# Qwiic_GPS-RTK2_-_ublox_ZED-F9P.net
KiCad netlist of a schematic drawn in EAGLE
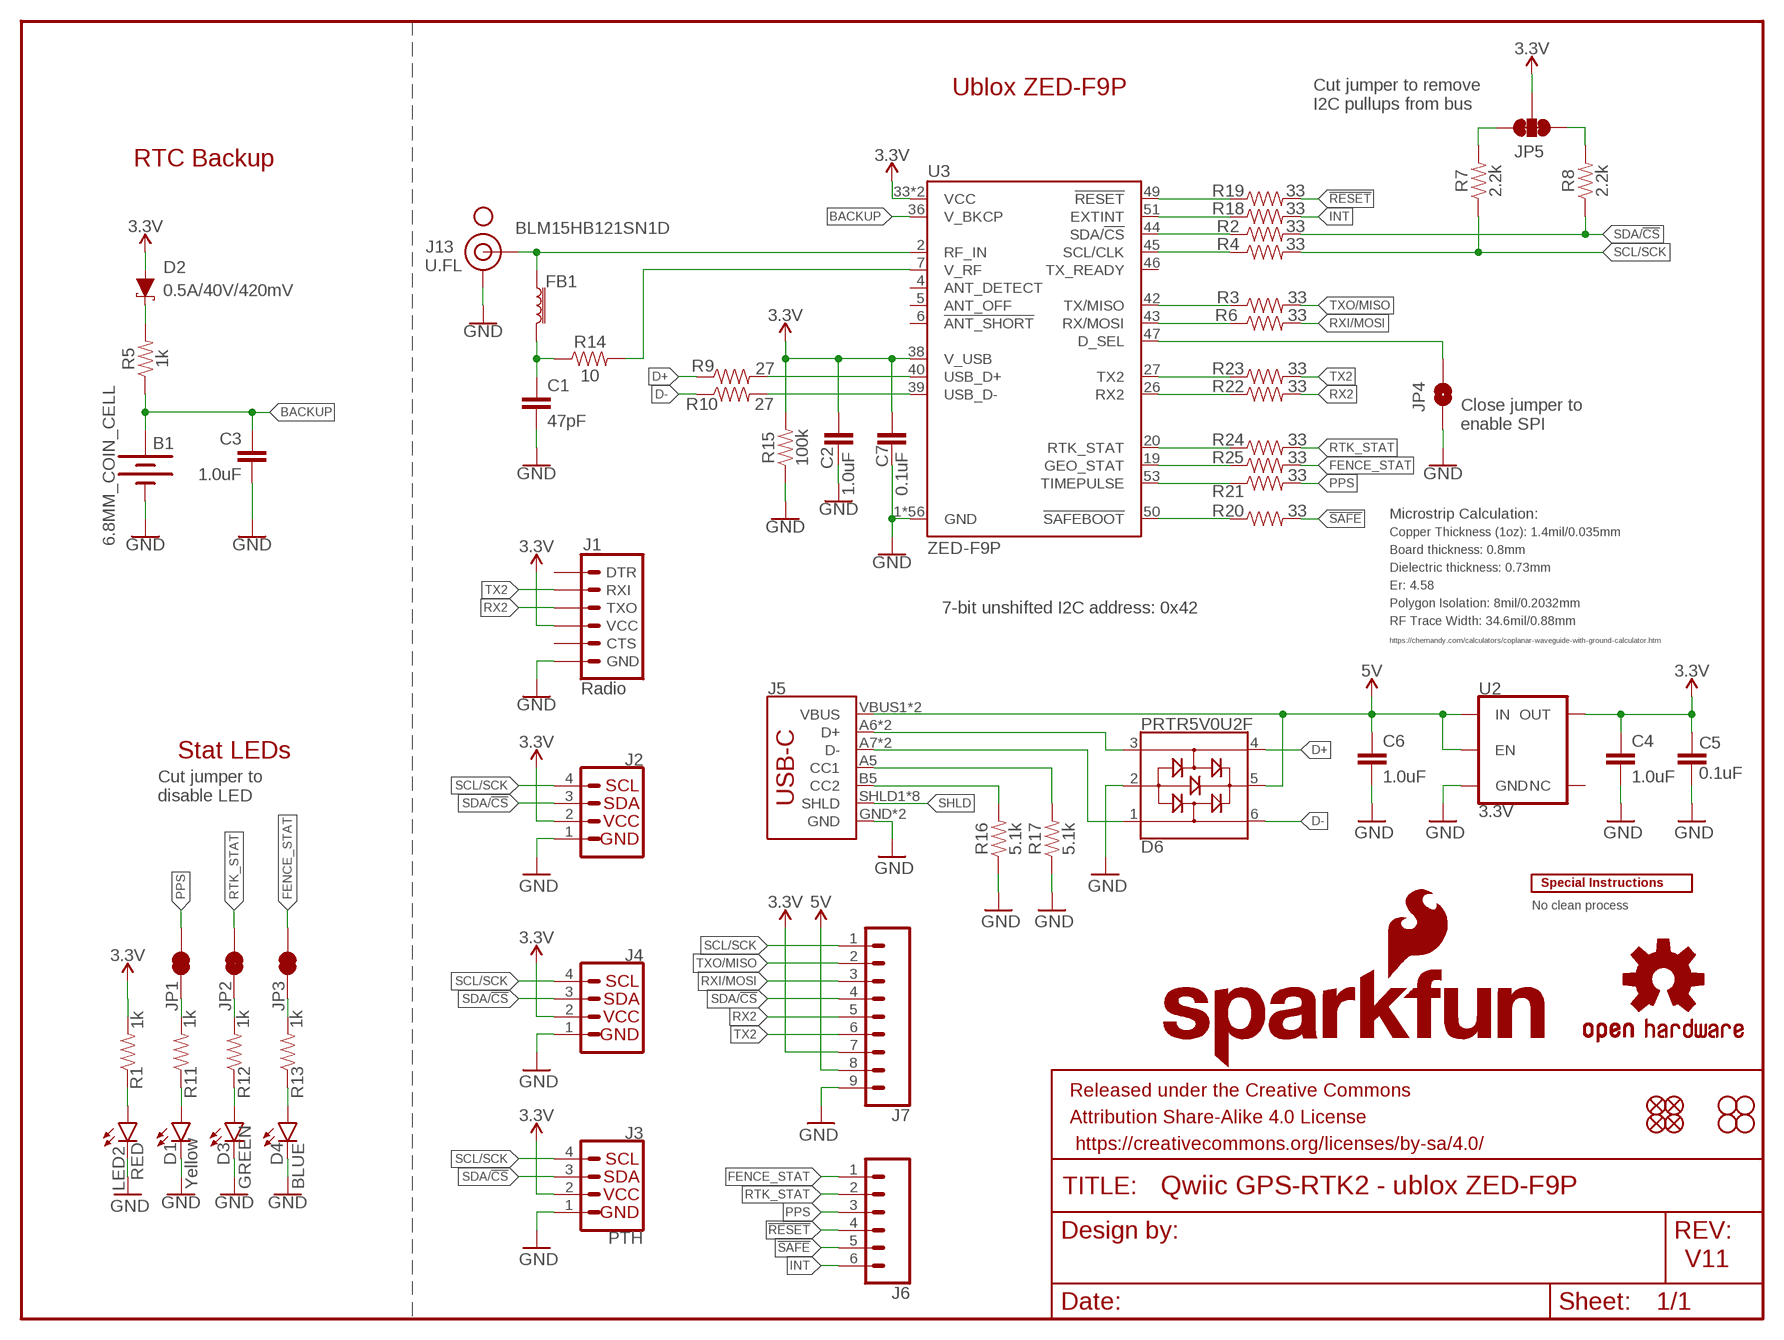
[diagram p0: schematic, sheet 1]

(export (version "E")
  (design (tool "Eeschema 10.0.6"))
  (components
    (comp (ref "B1")
      (value "6.8MM_COIN_CELL")
      (footprint "eagle-import:BATTCON-6.8MM")
      (libsource (lib "eagle-import") (part "BATTERY-6.8MM_SMD"))
    )
    (comp (ref "C1")
      (value "47pF")
      (footprint "eagle-import:0603")
      (libsource (lib "eagle-import") (part "47PF-0603-50V-5%"))
    )
    (comp (ref "C2")
      (value "1.0uF")
      (footprint "eagle-import:0603")
      (libsource (lib "eagle-import") (part "1.0UF-0603-16V-10%"))
    )
    (comp (ref "C3")
      (value "1.0uF")
      (footprint "eagle-import:0603")
      (libsource (lib "eagle-import") (part "1.0UF-0603-16V-10%"))
    )
    (comp (ref "C4")
      (value "1.0uF")
      (footprint "eagle-import:0603")
      (libsource (lib "eagle-import") (part "1.0UF-0603-16V-10%"))
    )
    (comp (ref "C5")
      (value "0.1uF")
      (footprint "eagle-import:0603")
      (libsource (lib "eagle-import") (part "0.1UF-0603-25V-(+80/-20%)"))
    )
    (comp (ref "C6")
      (value "1.0uF")
      (footprint "eagle-import:0603")
      (libsource (lib "eagle-import") (part "1.0UF-0603-16V-10%"))
    )
    (comp (ref "C7")
      (value "0.1uF")
      (footprint "eagle-import:0603")
      (libsource (lib "eagle-import") (part "0.1UF-0603-25V-(+80/-20%)"))
    )
    (comp (ref "D1")
      (value "Yellow")
      (footprint "eagle-import:LED-0603")
      (libsource (lib "eagle-import") (part "LED-YELLOW0603"))
    )
    (comp (ref "D2")
      (value "0.5A/40V/420mV")
      (footprint "eagle-import:SOD-323")
      (libsource (lib "eagle-import") (part "DIODE-SCHOTTKY-PMEG4005EJ"))
    )
    (comp (ref "D3")
      (value "GREEN")
      (footprint "eagle-import:LED-0603")
      (libsource (lib "eagle-import") (part "LED-GREEN0603"))
    )
    (comp (ref "D4")
      (value "BLUE")
      (footprint "eagle-import:LED-0603")
      (libsource (lib "eagle-import") (part "LED-BLUE0603"))
    )
    (comp (ref "D6")
      (value "PRTR5V0U2F")
      (footprint "eagle-import:SOT886")
      (libsource (lib "eagle-import") (part "PRTR5V0U2F"))
    )
    (comp (ref "FB1")
      (value "FERRITE_BEAD-120_OHM-0402")
      (footprint "eagle-import:0402")
      (fields (field (name "MFG_PART") "BLM15HB121SN1D"))
      (libsource (lib "eagle-import") (part "FERRITE_BEAD-120_OHM-0402"))
    )
    (comp (ref "FRAME1")
      (value "FRAME-LETTER")
      (footprint "eagle-import:CREATIVE_COMMONS")
      (libsource (lib "eagle-import") (part "FRAME-LETTER"))
    )
    (comp (ref "J1")
      (value "Radio")
      (footprint "eagle-import:1X06_NO_SILK")
      (libsource (lib "eagle-import") (part "6_PIN_SERIAL_TARGET_NO_SILK"))
    )
    (comp (ref "J2")
      (value "I2C_STANDARDQWIIC")
      (footprint "eagle-import:1X04_1MM_RA")
      (libsource (lib "eagle-import") (part "I2C_STANDARDQWIIC"))
    )
    (comp (ref "J3")
      (value "PTH")
      (footprint "eagle-import:1X04_NO_SILK")
      (libsource (lib "eagle-import") (part "SparkX_I2C_STANDARD_NO_SILK"))
    )
    (comp (ref "J4")
      (value "I2C_STANDARDQWIIC")
      (footprint "eagle-import:1X04_1MM_RA")
      (libsource (lib "eagle-import") (part "I2C_STANDARDQWIIC"))
    )
    (comp (ref "J5")
      (value "USB_C16PIN")
      (footprint "eagle-import:USB-C-16P")
      (libsource (lib "eagle-import") (part "USB_C16PIN"))
    )
    (comp (ref "J6")
      (value "CONN_06NO_SILK_FEMALE_PTH")
      (footprint "eagle-import:1X06_NO_SILK")
      (libsource (lib "eagle-import") (part "CONN_06NO_SILK_FEMALE_PTH"))
    )
    (comp (ref "J7")
      (value "CONN_09NO_SILK")
      (footprint "eagle-import:1X09_NO_SILK")
      (libsource (lib "eagle-import") (part "CONN_09NO_SILK"))
    )
    (comp (ref "J13")
      (value "U.FL")
      (footprint "eagle-import:U.FL")
      (libsource (lib "eagle-import") (part "U.FL2PIN"))
    )
    (comp (ref "JP1")
      (value "JUMPER-SMT_2_NC_TRACE_SILK")
      (footprint "eagle-import:SMT-JUMPER_2_NC_TRACE_SILK")
      (libsource (lib "eagle-import") (part "JUMPER-SMT_2_NC_TRACE_SILK"))
    )
    (comp (ref "JP2")
      (value "JUMPER-SMT_2_NC_TRACE_SILK")
      (footprint "eagle-import:SMT-JUMPER_2_NC_TRACE_SILK")
      (libsource (lib "eagle-import") (part "JUMPER-SMT_2_NC_TRACE_SILK"))
    )
    (comp (ref "JP3")
      (value "JUMPER-SMT_2_NC_TRACE_SILK")
      (footprint "eagle-import:SMT-JUMPER_2_NC_TRACE_SILK")
      (libsource (lib "eagle-import") (part "JUMPER-SMT_2_NC_TRACE_SILK"))
    )
    (comp (ref "JP4")
      (value "JUMPER-SMT_2_NO_SILK")
      (footprint "eagle-import:SMT-JUMPER_2_NO_SILK")
      (libsource (lib "eagle-import") (part "JUMPER-SMT_2_NO_SILK"))
    )
    (comp (ref "JP5")
      (value "JUMPER-SMT_3_2-NC_TRACE_SILK")
      (footprint "eagle-import:SMT-JUMPER_3_2-NC_TRACE_SILK")
      (libsource (lib "eagle-import") (part "JUMPER-SMT_3_2-NC_TRACE_SILK"))
    )
    (comp (ref "JP21")
      (value "FIDUCIALUFIDUCIAL")
      (footprint "eagle-import:MICRO-FIDUCIAL")
      (libsource (lib "eagle-import") (part "FIDUCIALUFIDUCIAL"))
    )
    (comp (ref "JP31")
      (value "STAND-OFF")
      (footprint "eagle-import:STAND-OFF")
      (libsource (lib "eagle-import") (part "STAND-OFF"))
    )
    (comp (ref "JP41")
      (value "STAND-OFF")
      (footprint "eagle-import:STAND-OFF")
      (libsource (lib "eagle-import") (part "STAND-OFF"))
    )
    (comp (ref "JP61")
      (value "FIDUCIALUFIDUCIAL")
      (footprint "eagle-import:MICRO-FIDUCIAL")
      (libsource (lib "eagle-import") (part "FIDUCIALUFIDUCIAL"))
    )
    (comp (ref "JP71")
      (value "FIDUCIALUFIDUCIAL")
      (footprint "eagle-import:MICRO-FIDUCIAL")
      (libsource (lib "eagle-import") (part "FIDUCIALUFIDUCIAL"))
    )
    (comp (ref "JP81")
      (value "FIDUCIALUFIDUCIAL")
      (footprint "eagle-import:MICRO-FIDUCIAL")
      (libsource (lib "eagle-import") (part "FIDUCIALUFIDUCIAL"))
    )
    (comp (ref "JP91")
      (value "STAND-OFF")
      (footprint "eagle-import:STAND-OFF")
      (libsource (lib "eagle-import") (part "STAND-OFF"))
    )
    (comp (ref "JP101")
      (value "STAND-OFF")
      (footprint "eagle-import:STAND-OFF")
      (libsource (lib "eagle-import") (part "STAND-OFF"))
    )
    (comp (ref "LED2")
      (value "RED")
      (footprint "eagle-import:LED-0603")
      (libsource (lib "eagle-import") (part "LED-RED0603"))
    )
    (comp (ref "LOGO1")
      (value "OSHW-LOGOMINI")
      (footprint "eagle-import:OSHW-LOGO-MINI")
      (libsource (lib "eagle-import") (part "OSHW-LOGOMINI"))
    )
    (comp (ref "LOGO2")
      (value "SFE_LOGO_NAME_FLAME.1_INCH")
      (footprint "eagle-import:SFE_LOGO_NAME_FLAME_.1")
      (libsource (lib "eagle-import") (part "SFE_LOGO_NAME_FLAME.1_INCH"))
    )
    (comp (ref "R1")
      (value "1k")
      (footprint "eagle-import:0603")
      (libsource (lib "eagle-import") (part "1KOHM-0603-1/10W-1%"))
    )
    (comp (ref "R2")
      (value "33")
      (footprint "eagle-import:0603")
      (libsource (lib "eagle-import") (part "33OHM-0603-1/10W-1%"))
    )
    (comp (ref "R3")
      (value "33")
      (footprint "eagle-import:0603")
      (libsource (lib "eagle-import") (part "33OHM-0603-1/10W-1%"))
    )
    (comp (ref "R4")
      (value "33")
      (footprint "eagle-import:0603")
      (libsource (lib "eagle-import") (part "33OHM-0603-1/10W-1%"))
    )
    (comp (ref "R5")
      (value "1k")
      (footprint "eagle-import:0603")
      (libsource (lib "eagle-import") (part "1KOHM-0603-1/10W-1%"))
    )
    (comp (ref "R6")
      (value "33")
      (footprint "eagle-import:0603")
      (libsource (lib "eagle-import") (part "33OHM-0603-1/10W-1%"))
    )
    (comp (ref "R7")
      (value "2.2k")
      (footprint "eagle-import:0603")
      (libsource (lib "eagle-import") (part "2.2KOHM-0603-1/10W-1%"))
    )
    (comp (ref "R8")
      (value "2.2k")
      (footprint "eagle-import:0603")
      (libsource (lib "eagle-import") (part "2.2KOHM-0603-1/10W-1%"))
    )
    (comp (ref "R9")
      (value "27")
      (footprint "eagle-import:0603")
      (libsource (lib "eagle-import") (part "27OHM-0603-1/10W-1%"))
    )
    (comp (ref "R10")
      (value "27")
      (footprint "eagle-import:0603")
      (libsource (lib "eagle-import") (part "27OHM-0603-1/10W-1%"))
    )
    (comp (ref "R11")
      (value "1k")
      (footprint "eagle-import:0603")
      (libsource (lib "eagle-import") (part "1KOHM-0603-1/10W-1%"))
    )
    (comp (ref "R12")
      (value "1k")
      (footprint "eagle-import:0603")
      (libsource (lib "eagle-import") (part "1KOHM-0603-1/10W-1%"))
    )
    (comp (ref "R13")
      (value "1k")
      (footprint "eagle-import:0603")
      (libsource (lib "eagle-import") (part "1KOHM-0603-1/10W-1%"))
    )
    (comp (ref "R14")
      (value "10")
      (footprint "eagle-import:0603")
      (libsource (lib "eagle-import") (part "10OHM-0603-1/10W-1%"))
    )
    (comp (ref "R15")
      (value "100k")
      (footprint "eagle-import:0603")
      (libsource (lib "eagle-import") (part "100KOHM-0603-1/10W-1%"))
    )
    (comp (ref "R16")
      (value "5.1k")
      (footprint "eagle-import:0603")
      (libsource (lib "eagle-import") (part "5.1KOHM5.1KOHM-0603-1/10W-1%"))
    )
    (comp (ref "R17")
      (value "5.1k")
      (footprint "eagle-import:0603")
      (libsource (lib "eagle-import") (part "5.1KOHM5.1KOHM-0603-1/10W-1%"))
    )
    (comp (ref "R18")
      (value "33")
      (footprint "eagle-import:0603")
      (libsource (lib "eagle-import") (part "33OHM-0603-1/10W-1%"))
    )
    (comp (ref "R19")
      (value "33")
      (footprint "eagle-import:0603")
      (libsource (lib "eagle-import") (part "33OHM-0603-1/10W-1%"))
    )
    (comp (ref "R20")
      (value "33")
      (footprint "eagle-import:0603")
      (libsource (lib "eagle-import") (part "33OHM-0603-1/10W-1%"))
    )
    (comp (ref "R21")
      (value "33")
      (footprint "eagle-import:0603")
      (libsource (lib "eagle-import") (part "33OHM-0603-1/10W-1%"))
    )
    (comp (ref "R22")
      (value "33")
      (footprint "eagle-import:0603")
      (libsource (lib "eagle-import") (part "33OHM-0603-1/10W-1%"))
    )
    (comp (ref "R23")
      (value "33")
      (footprint "eagle-import:0603")
      (libsource (lib "eagle-import") (part "33OHM-0603-1/10W-1%"))
    )
    (comp (ref "R24")
      (value "33")
      (footprint "eagle-import:0603")
      (libsource (lib "eagle-import") (part "33OHM-0603-1/10W-1%"))
    )
    (comp (ref "R25")
      (value "33")
      (footprint "eagle-import:0603")
      (libsource (lib "eagle-import") (part "33OHM-0603-1/10W-1%"))
    )
    (comp (ref "U$2")
      (value "SPECIAL_INSTRUCTIONS-ORDERING")
      (footprint "eagle-import:ORDERING_INSTRUCTIONS")
      (libsource (lib "eagle-import") (part "SPECIAL_INSTRUCTIONS-ORDERING"))
    )
    (comp (ref "U$54")
      (value "SMA-ANTENNA-THREADED")
      (footprint "eagle-import:SMA-THREADED")
      (libsource (lib "eagle-import") (part "SMA-ANTENNA-THREADED"))
    )
    (comp (ref "U2")
      (value "3.3V")
      (footprint "eagle-import:SOT23-5")
      (libsource (lib "eagle-import") (part "V_REG_AP2112K-3.3V"))
    )
    (comp (ref "U3")
      (value "ZED-F9P")
      (footprint "eagle-import:ZED-F9P")
      (libsource (lib "eagle-import") (part "ZED-F9P"))
    )
  )
  (nets
    (net (code "1") (name "/SDA{slash}~{CS}") (class "Default")
      (node (ref "J2") (pin "3") (pinfunction "3_3") (pintype "passive"))
      (node (ref "J3") (pin "3") (pinfunction "SDA_3") (pintype "passive"))
      (node (ref "J4") (pin "3") (pinfunction "3_3") (pintype "passive"))
      (node (ref "J7") (pin "4") (pinfunction "4_4") (pintype "passive"))
      (node (ref "R2") (pin "2") (pinfunction "2_2") (pintype "passive"))
      (node (ref "R8") (pin "1") (pinfunction "1_1") (pintype "passive"))
    )
    (net (code "2") (name "/~{RESET}") (class "Default")
      (node (ref "J6") (pin "4") (pinfunction "4_4") (pintype "passive"))
      (node (ref "R19") (pin "2") (pinfunction "2_2") (pintype "passive"))
    )
    (net (code "3") (name "/~{SAFE}") (class "Default")
      (node (ref "J6") (pin "5") (pinfunction "5_5") (pintype "passive"))
      (node (ref "R20") (pin "2") (pinfunction "2_2") (pintype "passive"))
    )
    (net (code "4") (name "3.3V") (class "Default")
      (node (ref "C2") (pin "1") (pinfunction "1_1") (pintype "passive"))
      (node (ref "C4") (pin "1") (pinfunction "1_1") (pintype "passive"))
      (node (ref "C5") (pin "2") (pinfunction "2_2") (pintype "passive"))
      (node (ref "C7") (pin "2") (pinfunction "2_2") (pintype "passive"))
      (node (ref "D2") (pin "A") (pinfunction "A_A") (pintype "passive"))
      (node (ref "J1") (pin "4") (pinfunction "VCC_4") (pintype "passive"))
      (node (ref "J2") (pin "2") (pinfunction "2_2") (pintype "power_in"))
      (node (ref "J3") (pin "2") (pinfunction "VCC_2") (pintype "power_in"))
      (node (ref "J4") (pin "2") (pinfunction "2_2") (pintype "power_in"))
      (node (ref "J7") (pin "7") (pinfunction "7_7") (pintype "passive"))
      (node (ref "JP5") (pin "2") (pinfunction "2_2") (pintype "passive"))
      (node (ref "R1") (pin "2") (pinfunction "2_2") (pintype "passive"))
      (node (ref "R15") (pin "2") (pinfunction "2_2") (pintype "passive"))
      (node (ref "U2") (pin "5") (pinfunction "OUT_5") (pintype "passive"))
      (node (ref "U3") (pin "33") (pinfunction "VCC_33") (pintype "bidirectional"))
      (node (ref "U3") (pin "34") (pinfunction "VCC_34") (pintype "bidirectional"))
      (node (ref "U3") (pin "38") (pinfunction "V_USB_38") (pintype "bidirectional"))
    )
    (net (code "5") (name "5V") (class "Default")
      (node (ref "C6") (pin "1") (pinfunction "1_1") (pintype "passive"))
      (node (ref "D6") (pin "5") (pinfunction "5_5") (pintype "bidirectional"))
      (node (ref "J5") (pin "VBUS1") (pinfunction "VBUS_VBUS1") (pintype "bidirectional"))
      (node (ref "J5") (pin "VBUS2") (pinfunction "VBUS_VBUS2") (pintype "bidirectional"))
      (node (ref "J7") (pin "8") (pinfunction "8_8") (pintype "passive"))
      (node (ref "U2") (pin "1") (pinfunction "IN_1") (pintype "input"))
      (node (ref "U2") (pin "3") (pinfunction "EN_3") (pintype "input"))
    )
    (net (code "6") (name "BACKUP") (class "Default")
      (node (ref "B1") (pin "+") (pinfunction "+_+") (pintype "power_in"))
      (node (ref "C3") (pin "1") (pinfunction "1_1") (pintype "passive"))
      (node (ref "R5") (pin "1") (pinfunction "1_1") (pintype "passive"))
      (node (ref "U3") (pin "36") (pinfunction "V_BKCP_36") (pintype "bidirectional"))
    )
    (net (code "7") (name "D+") (class "Default")
      (node (ref "D6") (pin "4") (pinfunction "4_4") (pintype "bidirectional"))
      (node (ref "R9") (pin "1") (pinfunction "1_1") (pintype "passive"))
    )
    (net (code "8") (name "D-") (class "Default")
      (node (ref "D6") (pin "6") (pinfunction "6_6") (pintype "bidirectional"))
      (node (ref "R10") (pin "1") (pinfunction "1_1") (pintype "passive"))
    )
    (net (code "9") (name "FENCE_STAT") (class "Default")
      (node (ref "J6") (pin "1") (pinfunction "1_1") (pintype "passive"))
      (node (ref "JP3") (pin "2") (pinfunction "2_2") (pintype "passive"))
      (node (ref "R25") (pin "2") (pinfunction "2_2") (pintype "passive"))
    )
    (net (code "10") (name "GND") (class "Default")
      (node (ref "B1") (pin "-") (pinfunction "-_-") (pintype "power_in"))
      (node (ref "C1") (pin "2") (pinfunction "2_2") (pintype "passive"))
      (node (ref "C2") (pin "2") (pinfunction "2_2") (pintype "passive"))
      (node (ref "C3") (pin "2") (pinfunction "2_2") (pintype "passive"))
      (node (ref "C4") (pin "2") (pinfunction "2_2") (pintype "passive"))
      (node (ref "C5") (pin "1") (pinfunction "1_1") (pintype "passive"))
      (node (ref "C6") (pin "2") (pinfunction "2_2") (pintype "passive"))
      (node (ref "C7") (pin "1") (pinfunction "1_1") (pintype "passive"))
      (node (ref "D1") (pin "C") (pinfunction "C_C") (pintype "passive"))
      (node (ref "D3") (pin "C") (pinfunction "C_C") (pintype "passive"))
      (node (ref "D4") (pin "C") (pinfunction "C_C") (pintype "passive"))
      (node (ref "D6") (pin "2") (pinfunction "2_2") (pintype "bidirectional"))
      (node (ref "J1") (pin "6") (pinfunction "GND_6") (pintype "passive"))
      (node (ref "J13") (pin "1") (pinfunction "GND_1") (pintype "bidirectional"))
      (node (ref "J13") (pin "2") (pinfunction "GND_2") (pintype "bidirectional"))
      (node (ref "J2") (pin "1") (pinfunction "1_1") (pintype "power_in"))
      (node (ref "J3") (pin "1") (pinfunction "GND_1") (pintype "power_in"))
      (node (ref "J4") (pin "1") (pinfunction "1_1") (pintype "power_in"))
      (node (ref "J5") (pin "GND") (pinfunction "GND_GND") (pintype "bidirectional"))
      (node (ref "J5") (pin "GND2") (pinfunction "GND_GND2") (pintype "bidirectional"))
      (node (ref "J7") (pin "9") (pinfunction "9_9") (pintype "passive"))
      (node (ref "JP4") (pin "1") (pinfunction "1_1") (pintype "passive"))
      (node (ref "LED2") (pin "C") (pinfunction "C_C") (pintype "passive"))
      (node (ref "R15") (pin "1") (pinfunction "1_1") (pintype "passive"))
      (node (ref "R16") (pin "1") (pinfunction "1_1") (pintype "passive"))
      (node (ref "R17") (pin "1") (pinfunction "1_1") (pintype "passive"))
      (node (ref "U2") (pin "2") (pinfunction "GND_2") (pintype "input"))
      (node (ref "U3") (pin "1") (pinfunction "GND_1") (pintype "bidirectional"))
      (node (ref "U3") (pin "100") (pinfunction "GND_100") (pintype "bidirectional"))
      (node (ref "U3") (pin "101") (pinfunction "GND_101") (pintype "bidirectional"))
      (node (ref "U3") (pin "102") (pinfunction "GND_102") (pintype "bidirectional"))
      (node (ref "U3") (pin "12") (pinfunction "GND_12") (pintype "bidirectional"))
      (node (ref "U3") (pin "14") (pinfunction "GND_14") (pintype "bidirectional"))
      (node (ref "U3") (pin "3") (pinfunction "GND_3") (pintype "bidirectional"))
      (node (ref "U3") (pin "32") (pinfunction "GND_32") (pintype "bidirectional"))
      (node (ref "U3") (pin "37") (pinfunction "GND_37") (pintype "bidirectional"))
      (node (ref "U3") (pin "41") (pinfunction "GND_41") (pintype "bidirectional"))
      (node (ref "U3") (pin "48") (pinfunction "GND_48") (pintype "bidirectional"))
      (node (ref "U3") (pin "55") (pinfunction "GND_55") (pintype "bidirectional"))
      (node (ref "U3") (pin "56") (pinfunction "GND_56") (pintype "bidirectional"))
      (node (ref "U3") (pin "57") (pinfunction "GND_57") (pintype "bidirectional"))
      (node (ref "U3") (pin "58") (pinfunction "GND_58") (pintype "bidirectional"))
      (node (ref "U3") (pin "59") (pinfunction "GND_59") (pintype "bidirectional"))
      (node (ref "U3") (pin "60") (pinfunction "GND_60") (pintype "bidirectional"))
      (node (ref "U3") (pin "61") (pinfunction "GND_61") (pintype "bidirectional"))
      (node (ref "U3") (pin "62") (pinfunction "GND_62") (pintype "bidirectional"))
      (node (ref "U3") (pin "63") (pinfunction "GND_63") (pintype "bidirectional"))
      (node (ref "U3") (pin "64") (pinfunction "GND_64") (pintype "bidirectional"))
      (node (ref "U3") (pin "65") (pinfunction "GND_65") (pintype "bidirectional"))
      (node (ref "U3") (pin "66") (pinfunction "GND_66") (pintype "bidirectional"))
      (node (ref "U3") (pin "67") (pinfunction "GND_67") (pintype "bidirectional"))
      (node (ref "U3") (pin "68") (pinfunction "GND_68") (pintype "bidirectional"))
      (node (ref "U3") (pin "69") (pinfunction "GND_69") (pintype "bidirectional"))
      (node (ref "U3") (pin "70") (pinfunction "GND_70") (pintype "bidirectional"))
      (node (ref "U3") (pin "71") (pinfunction "GND_71") (pintype "bidirectional"))
      (node (ref "U3") (pin "72") (pinfunction "GND_72") (pintype "bidirectional"))
      (node (ref "U3") (pin "73") (pinfunction "GND_73") (pintype "bidirectional"))
      (node (ref "U3") (pin "74") (pinfunction "GND_74") (pintype "bidirectional"))
      (node (ref "U3") (pin "75") (pinfunction "GND_75") (pintype "bidirectional"))
      (node (ref "U3") (pin "76") (pinfunction "GND_76") (pintype "bidirectional"))
      (node (ref "U3") (pin "77") (pinfunction "GND_77") (pintype "bidirectional"))
      (node (ref "U3") (pin "78") (pinfunction "GND_78") (pintype "bidirectional"))
      (node (ref "U3") (pin "79") (pinfunction "GND_79") (pintype "bidirectional"))
      (node (ref "U3") (pin "80") (pinfunction "GND_80") (pintype "bidirectional"))
      (node (ref "U3") (pin "81") (pinfunction "GND_81") (pintype "bidirectional"))
      (node (ref "U3") (pin "82") (pinfunction "GND_82") (pintype "bidirectional"))
      (node (ref "U3") (pin "83") (pinfunction "GND_83") (pintype "bidirectional"))
      (node (ref "U3") (pin "84") (pinfunction "GND_84") (pintype "bidirectional"))
      (node (ref "U3") (pin "85") (pinfunction "GND_85") (pintype "bidirectional"))
      (node (ref "U3") (pin "86") (pinfunction "GND_86") (pintype "bidirectional"))
      (node (ref "U3") (pin "87") (pinfunction "GND_87") (pintype "bidirectional"))
      (node (ref "U3") (pin "88") (pinfunction "GND_88") (pintype "bidirectional"))
      (node (ref "U3") (pin "89") (pinfunction "GND_89") (pintype "bidirectional"))
      (node (ref "U3") (pin "90") (pinfunction "GND_90") (pintype "bidirectional"))
      (node (ref "U3") (pin "91") (pinfunction "GND_91") (pintype "bidirectional"))
      (node (ref "U3") (pin "92") (pinfunction "GND_92") (pintype "bidirectional"))
      (node (ref "U3") (pin "93") (pinfunction "GND_93") (pintype "bidirectional"))
      (node (ref "U3") (pin "94") (pinfunction "GND_94") (pintype "bidirectional"))
      (node (ref "U3") (pin "95") (pinfunction "GND_95") (pintype "bidirectional"))
      (node (ref "U3") (pin "96") (pinfunction "GND_96") (pintype "bidirectional"))
      (node (ref "U3") (pin "97") (pinfunction "GND_97") (pintype "bidirectional"))
      (node (ref "U3") (pin "98") (pinfunction "GND_98") (pintype "bidirectional"))
      (node (ref "U3") (pin "99") (pinfunction "GND_99") (pintype "bidirectional"))
    )
    (net (code "11") (name "INT") (class "Default")
      (node (ref "J6") (pin "6") (pinfunction "6_6") (pintype "passive"))
      (node (ref "R18") (pin "2") (pinfunction "2_2") (pintype "passive"))
    )
    (net (code "12") (name "Net-(C1-Pad1)") (class "Default")
      (node (ref "C1") (pin "1") (pinfunction "1_1") (pintype "passive"))
      (node (ref "FB1") (pin "2") (pinfunction "2_2") (pintype "passive"))
      (node (ref "R14") (pin "1") (pinfunction "1_1") (pintype "passive"))
    )
    (net (code "13") (name "Net-(D1-PadA)") (class "Default")
      (node (ref "D1") (pin "A") (pinfunction "A_A") (pintype "passive"))
      (node (ref "R11") (pin "1") (pinfunction "1_1") (pintype "passive"))
    )
    (net (code "14") (name "Net-(D2-PadC)") (class "Default")
      (node (ref "D2") (pin "C") (pinfunction "C_C") (pintype "passive"))
      (node (ref "R5") (pin "2") (pinfunction "2_2") (pintype "passive"))
    )
    (net (code "15") (name "Net-(D3-PadA)") (class "Default")
      (node (ref "D3") (pin "A") (pinfunction "A_A") (pintype "passive"))
      (node (ref "R12") (pin "1") (pinfunction "1_1") (pintype "passive"))
    )
    (net (code "16") (name "Net-(D4-PadA)") (class "Default")
      (node (ref "D4") (pin "A") (pinfunction "A_A") (pintype "passive"))
      (node (ref "R13") (pin "1") (pinfunction "1_1") (pintype "passive"))
    )
    (net (code "17") (name "Net-(D6-Pad1)") (class "Default")
      (node (ref "D6") (pin "1") (pinfunction "1_1") (pintype "bidirectional"))
      (node (ref "J5") (pin "A7") (pinfunction "D-_A7") (pintype "bidirectional"))
      (node (ref "J5") (pin "B7") (pinfunction "D-_B7") (pintype "bidirectional"))
    )
    (net (code "18") (name "Net-(D6-Pad3)") (class "Default")
      (node (ref "D6") (pin "3") (pinfunction "3_3") (pintype "bidirectional"))
      (node (ref "J5") (pin "A6") (pinfunction "D+_A6") (pintype "bidirectional"))
      (node (ref "J5") (pin "B6") (pinfunction "D+_B6") (pintype "bidirectional"))
    )
    (net (code "19") (name "Net-(J5-CC1)") (class "Default")
      (node (ref "J5") (pin "A5") (pinfunction "CC1_A5") (pintype "bidirectional"))
      (node (ref "R17") (pin "2") (pinfunction "2_2") (pintype "passive"))
    )
    (net (code "20") (name "Net-(J5-CC2)") (class "Default")
      (node (ref "J5") (pin "B5") (pinfunction "CC2_B5") (pintype "bidirectional"))
      (node (ref "R16") (pin "2") (pinfunction "2_2") (pintype "passive"))
    )
    (net (code "21") (name "Net-(J13-SIGNAL)") (class "Default")
      (node (ref "FB1") (pin "1") (pinfunction "1_1") (pintype "passive"))
      (node (ref "J13") (pin "FEED") (pinfunction "SIGNAL_FEED") (pintype "bidirectional"))
      (node (ref "U3") (pin "2") (pinfunction "RF_IN_2") (pintype "bidirectional"))
    )
    (net (code "22") (name "Net-(JP1-Pad1)") (class "Default")
      (node (ref "JP1") (pin "1") (pinfunction "1_1") (pintype "passive"))
      (node (ref "R11") (pin "2") (pinfunction "2_2") (pintype "passive"))
    )
    (net (code "23") (name "Net-(JP2-Pad1)") (class "Default")
      (node (ref "JP2") (pin "1") (pinfunction "1_1") (pintype "passive"))
      (node (ref "R12") (pin "2") (pinfunction "2_2") (pintype "passive"))
    )
    (net (code "24") (name "Net-(JP3-Pad1)") (class "Default")
      (node (ref "JP3") (pin "1") (pinfunction "1_1") (pintype "passive"))
      (node (ref "R13") (pin "2") (pinfunction "2_2") (pintype "passive"))
    )
    (net (code "25") (name "Net-(JP5-Pad1)") (class "Default")
      (node (ref "JP5") (pin "1") (pinfunction "1_1") (pintype "passive"))
      (node (ref "R8") (pin "2") (pinfunction "2_2") (pintype "passive"))
    )
    (net (code "26") (name "Net-(JP5-Pad3)") (class "Default")
      (node (ref "JP5") (pin "3") (pinfunction "3_3") (pintype "passive"))
      (node (ref "R7") (pin "2") (pinfunction "2_2") (pintype "passive"))
    )
    (net (code "27") (name "Net-(LED2-PadA)") (class "Default")
      (node (ref "LED2") (pin "A") (pinfunction "A_A") (pintype "passive"))
      (node (ref "R1") (pin "1") (pinfunction "1_1") (pintype "passive"))
    )
    (net (code "28") (name "Net-(U3-D_SEL)") (class "Default")
      (node (ref "JP4") (pin "2") (pinfunction "2_2") (pintype "passive"))
      (node (ref "U3") (pin "47") (pinfunction "D_SEL_47") (pintype "bidirectional"))
    )
    (net (code "29") (name "Net-(U3-EXTINT)") (class "Default")
      (node (ref "R18") (pin "1") (pinfunction "1_1") (pintype "passive"))
      (node (ref "U3") (pin "51") (pinfunction "EXTINT_51") (pintype "bidirectional"))
    )
    (net (code "30") (name "Net-(U3-GEO_STAT)") (class "Default")
      (node (ref "R25") (pin "1") (pinfunction "1_1") (pintype "passive"))
      (node (ref "U3") (pin "19") (pinfunction "GEO_STAT_19") (pintype "bidirectional"))
    )
    (net (code "31") (name "Net-(U3-RTK_STAT)") (class "Default")
      (node (ref "R24") (pin "1") (pinfunction "1_1") (pintype "passive"))
      (node (ref "U3") (pin "20") (pinfunction "RTK_STAT_20") (pintype "bidirectional"))
    )
    (net (code "32") (name "Net-(U3-RX2)") (class "Default")
      (node (ref "R22") (pin "1") (pinfunction "1_1") (pintype "passive"))
      (node (ref "U3") (pin "26") (pinfunction "RX2_26") (pintype "bidirectional"))
    )
    (net (code "33") (name "Net-(U3-RX{slash}MOSI)") (class "Default")
      (node (ref "R6") (pin "1") (pinfunction "1_1") (pintype "passive"))
      (node (ref "U3") (pin "43") (pinfunction "RX/MOSI_43") (pintype "bidirectional"))
    )
    (net (code "34") (name "Net-(U3-SCL{slash}CLK)") (class "Default")
      (node (ref "R4") (pin "1") (pinfunction "1_1") (pintype "passive"))
      (node (ref "U3") (pin "45") (pinfunction "SCL/CLK_45") (pintype "bidirectional"))
    )
    (net (code "35") (name "Net-(U3-SDA{slash}~{CS})") (class "Default")
      (node (ref "R2") (pin "1") (pinfunction "1_1") (pintype "passive"))
      (node (ref "U3") (pin "44") (pinfunction "SDA/~{CS}_44") (pintype "bidirectional"))
    )
    (net (code "36") (name "Net-(U3-TIMEPULSE)") (class "Default")
      (node (ref "R21") (pin "1") (pinfunction "1_1") (pintype "passive"))
      (node (ref "U3") (pin "53") (pinfunction "TIMEPULSE_53") (pintype "bidirectional"))
    )
    (net (code "37") (name "Net-(U3-TX2)") (class "Default")
      (node (ref "R23") (pin "1") (pinfunction "1_1") (pintype "passive"))
      (node (ref "U3") (pin "27") (pinfunction "TX2_27") (pintype "bidirectional"))
    )
    (net (code "38") (name "Net-(U3-TX{slash}MISO)") (class "Default")
      (node (ref "R3") (pin "1") (pinfunction "1_1") (pintype "passive"))
      (node (ref "U3") (pin "42") (pinfunction "TX/MISO_42") (pintype "bidirectional"))
    )
    (net (code "39") (name "Net-(U3-USB_D+)") (class "Default")
      (node (ref "R9") (pin "2") (pinfunction "2_2") (pintype "passive"))
      (node (ref "U3") (pin "40") (pinfunction "USB_D+_40") (pintype "bidirectional"))
    )
    (net (code "40") (name "Net-(U3-USB_D-)") (class "Default")
      (node (ref "R10") (pin "2") (pinfunction "2_2") (pintype "passive"))
      (node (ref "U3") (pin "39") (pinfunction "USB_D-_39") (pintype "bidirectional"))
    )
    (net (code "41") (name "Net-(U3-V_RF)") (class "Default")
      (node (ref "R14") (pin "2") (pinfunction "2_2") (pintype "passive"))
      (node (ref "U3") (pin "7") (pinfunction "V_RF_7") (pintype "bidirectional"))
    )
    (net (code "42") (name "Net-(U3-~{RESET})") (class "Default")
      (node (ref "R19") (pin "1") (pinfunction "1_1") (pintype "passive"))
      (node (ref "U3") (pin "49") (pinfunction "~{RESET}_49") (pintype "bidirectional"))
    )
    (net (code "43") (name "Net-(U3-~{SAFEBOOT})") (class "Default")
      (node (ref "R20") (pin "1") (pinfunction "1_1") (pintype "passive"))
      (node (ref "U3") (pin "50") (pinfunction "~{SAFEBOOT}_50") (pintype "bidirectional"))
    )
    (net (code "44") (name "PPS") (class "Default")
      (node (ref "J6") (pin "3") (pinfunction "3_3") (pintype "passive"))
      (node (ref "JP1") (pin "2") (pinfunction "2_2") (pintype "passive"))
      (node (ref "R21") (pin "2") (pinfunction "2_2") (pintype "passive"))
    )
    (net (code "45") (name "RTK_STAT") (class "Default")
      (node (ref "J6") (pin "2") (pinfunction "2_2") (pintype "passive"))
      (node (ref "JP2") (pin "2") (pinfunction "2_2") (pintype "passive"))
      (node (ref "R24") (pin "2") (pinfunction "2_2") (pintype "passive"))
    )
    (net (code "46") (name "RX2") (class "Default")
      (node (ref "J1") (pin "3") (pinfunction "TXO_3") (pintype "passive"))
      (node (ref "J7") (pin "5") (pinfunction "5_5") (pintype "passive"))
      (node (ref "R22") (pin "2") (pinfunction "2_2") (pintype "passive"))
    )
    (net (code "47") (name "RXI{slash}MOSI") (class "Default")
      (node (ref "J7") (pin "3") (pinfunction "3_3") (pintype "passive"))
      (node (ref "R6") (pin "2") (pinfunction "2_2") (pintype "passive"))
    )
    (net (code "48") (name "SCL{slash}SCK") (class "Default")
      (node (ref "J2") (pin "4") (pinfunction "4_4") (pintype "passive"))
      (node (ref "J3") (pin "4") (pinfunction "SCL_4") (pintype "passive"))
      (node (ref "J4") (pin "4") (pinfunction "4_4") (pintype "passive"))
      (node (ref "J7") (pin "1") (pinfunction "1_1") (pintype "passive"))
      (node (ref "R4") (pin "2") (pinfunction "2_2") (pintype "passive"))
      (node (ref "R7") (pin "1") (pinfunction "1_1") (pintype "passive"))
    )
    (net (code "49") (name "SHLD") (class "Default")
      (node (ref "J5") (pin "SHLD1") (pinfunction "SHLD_SHLD1") (pintype "bidirectional"))
      (node (ref "J5") (pin "SHLD2") (pinfunction "SHLD_SHLD2") (pintype "bidirectional"))
      (node (ref "J5") (pin "SHLD3") (pinfunction "SHLD_SHLD3") (pintype "bidirectional"))
      (node (ref "J5") (pin "SHLD4") (pinfunction "SHLD_SHLD4") (pintype "bidirectional"))
      (node (ref "J5") (pin "SHLD5") (pinfunction "SHLD_SHLD5") (pintype "bidirectional"))
      (node (ref "J5") (pin "SHLD6") (pinfunction "SHLD_SHLD6") (pintype "bidirectional"))
      (node (ref "J5") (pin "SHLD7") (pinfunction "SHLD_SHLD7") (pintype "bidirectional"))
      (node (ref "J5") (pin "SHLD8") (pinfunction "SHLD_SHLD8") (pintype "bidirectional"))
    )
    (net (code "50") (name "TX2") (class "Default")
      (node (ref "J1") (pin "2") (pinfunction "RXI_2") (pintype "passive"))
      (node (ref "J7") (pin "6") (pinfunction "6_6") (pintype "passive"))
      (node (ref "R23") (pin "2") (pinfunction "2_2") (pintype "passive"))
    )
    (net (code "51") (name "TXO{slash}MISO") (class "Default")
      (node (ref "J7") (pin "2") (pinfunction "2_2") (pintype "passive"))
      (node (ref "R3") (pin "2") (pinfunction "2_2") (pintype "passive"))
    )
    (net (code "52") (name "unconnected-(J1-CTS-Pad5)") (class "Default")
      (node (ref "J1") (pin "5") (pinfunction "CTS_5") (pintype "passive"))
    )
    (net (code "53") (name "unconnected-(J1-DTR-Pad1)") (class "Default")
      (node (ref "J1") (pin "1") (pinfunction "DTR_1") (pintype "passive"))
    )
    (net (code "54") (name "unconnected-(U2-NC-Pad4)") (class "Default")
      (node (ref "U2") (pin "4") (pinfunction "NC_4") (pintype "no_connect"))
    )
    (net (code "55") (name "unconnected-(U3-ANT_DETECT-Pad4)") (class "Default")
      (node (ref "U3") (pin "4") (pinfunction "ANT_DETECT_4") (pintype "bidirectional"))
    )
    (net (code "56") (name "unconnected-(U3-ANT_OFF-Pad5)") (class "Default")
      (node (ref "U3") (pin "5") (pinfunction "ANT_OFF_5") (pintype "bidirectional"))
    )
    (net (code "57") (name "unconnected-(U3-TX_READY-Pad46)") (class "Default")
      (node (ref "U3") (pin "46") (pinfunction "TX_READY_46") (pintype "bidirectional"))
    )
    (net (code "58") (name "unconnected-(U3-~{ANT_SHORT}-Pad6)") (class "Default")
      (node (ref "U3") (pin "6") (pinfunction "~{ANT_SHORT}_6") (pintype "bidirectional"))
    )
  )
)
